# FTDI_Photosensor.net
KiCad netlist of a schematic drawn in Altium Designer
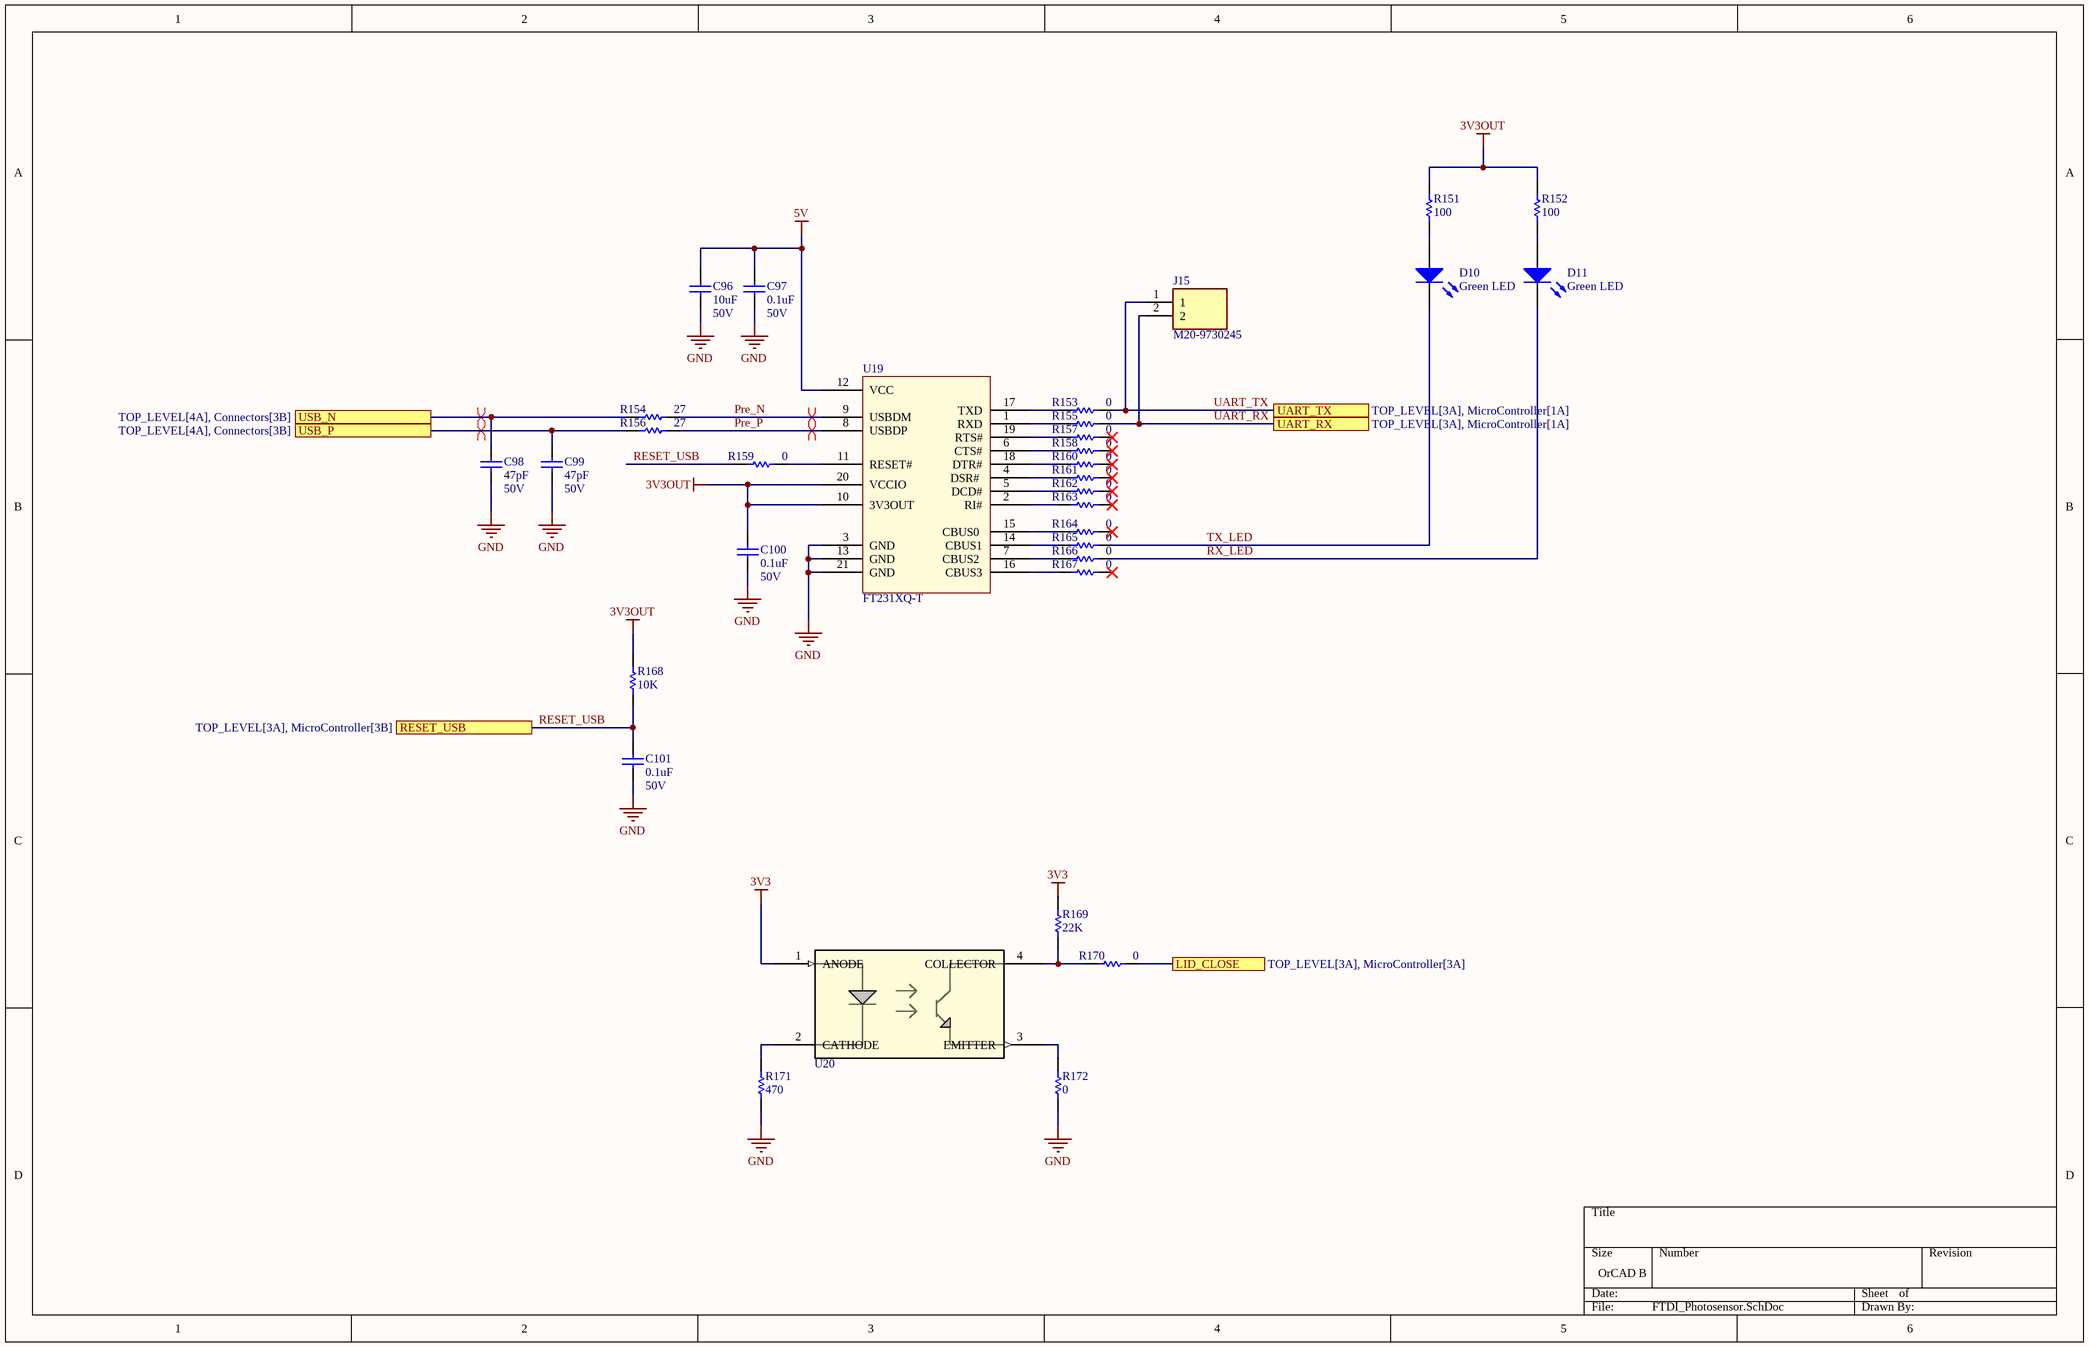
[diagram p0: FTDI_Photosensor.SchDoc]

(export (version "E")
  (design (tool "Eeschema 10.0.6"))
  (components
    (comp (ref "C96")
      (value "10uF")
      (footprint "DEFAULT_CAPACITOR_0805")
      (description "CAP CER 10UF 50V X5R 0805")
      (fields (field (name "RATING") "50V") (field (name "Comment") "GRM21BR61H106KE43L"))
      (libsource (lib "Avery Altium Llibrary") (part "GRM21BR61H106KE43L"))
    )
    (comp (ref "C97")
      (value "0.1uF")
      (footprint "DEFAULT_CAPACITOR_0805")
      (description "CAP CER 0.1UF 50V X7R 0805")
      (fields
        (field (name "MANUFACTURER") "Cal-Chip Electronics, Inc.")
        (field (name "RATING") "50V")
        (field (name "Comment") "KGM21NR71H104KT")
      )
      (libsource (lib "Avery Altium Llibrary") (part "KGM21NR71H104KT"))
    )
    (comp (ref "C98")
      (value "47pF")
      (footprint "DEFAULT_CAPACITOR_0805")
      (description "CAP CER 47PF 50V C0G/NP0 0805")
      (fields (field (name "RATING") "50V") (field (name "Comment") "C0805X470J5GACTU"))
      (libsource (lib "Avery Altium Llibrary") (part "C0805X470J5GACTU"))
    )
    (comp (ref "C99")
      (value "47pF")
      (footprint "DEFAULT_CAPACITOR_0805")
      (description "CAP CER 47PF 50V C0G/NP0 0805")
      (fields (field (name "RATING") "50V") (field (name "Comment") "C0805X470J5GACTU"))
      (libsource (lib "Avery Altium Llibrary") (part "C0805X470J5GACTU"))
    )
    (comp (ref "C100")
      (value "0.1uF")
      (footprint "DEFAULT_CAPACITOR_0805")
      (description "CAP CER 0.1UF 50V X7R 0805")
      (fields
        (field (name "MANUFACTURER") "Cal-Chip Electronics, Inc.")
        (field (name "RATING") "50V")
        (field (name "Comment") "KGM21NR71H104KT")
      )
      (libsource (lib "Avery Altium Llibrary") (part "KGM21NR71H104KT"))
    )
    (comp (ref "C101")
      (value "0.1uF")
      (footprint "DEFAULT_CAPACITOR_0805")
      (description "CAP CER 0.1UF 50V X7R 0805")
      (fields
        (field (name "MANUFACTURER") "Cal-Chip Electronics, Inc.")
        (field (name "RATING") "50V")
        (field (name "Comment") "KGM21NR71H104KT")
      )
      (libsource (lib "Avery Altium Llibrary") (part "KGM21NR71H104KT"))
    )
    (comp (ref "D10")
      (value "Green LED")
      (footprint "DEFAULT_RESISTOR_0805")
      (description "LED GREEN")
      (fields (field (name "MP") "Blue LED 0805") (field (name "Comment") "LSM0805452V"))
      (libsource (lib "Avery Schem Library") (part "LSM0805452V"))
    )
    (comp (ref "D11")
      (value "Green LED")
      (footprint "DEFAULT_RESISTOR_0805")
      (description "LED GREEN")
      (fields (field (name "MP") "Blue LED 0805") (field (name "Comment") "LSM0805452V"))
      (libsource (lib "Avery Schem Library") (part "LSM0805452V"))
    )
    (comp (ref "J15")
      (value "M20-9730245")
      (footprint "M209730245")
      (description "M20: 2 Pos Plug SIL Straight 3mm THT Connector 7mm pin Gold")
      (fields (field (name "MOUSER PART NUMBER") "855-M20-9730245"))
      (libsource (lib "Avery Altium Llibrary") (part "M20-9730245"))
    )
    (comp (ref "R151")
      (value "100")
      (footprint "DEFAULT_RESISTOR_0805")
      (description "RES SMD 100 OHM 1% 1/4W 0805")
      (fields (field (name "POWER") "1/4W") (field (name "TOLERANCE") "1%"))
      (libsource (lib "Avery Altium Llibrary") (part "CRCW0805100RFKEA"))
    )
    (comp (ref "R152")
      (value "100")
      (footprint "DEFAULT_RESISTOR_0805")
      (description "RES SMD 100 OHM 1% 1/4W 0805")
      (fields (field (name "POWER") "1/4W") (field (name "TOLERANCE") "1%"))
      (libsource (lib "Avery Altium Llibrary") (part "CRCW0805100RFKEA"))
    )
    (comp (ref "R153")
      (value "0")
      (footprint "DEFAULT_RESISTOR_0805")
      (description "RES 0 OHM JUMPER 1/8W 0805")
      (fields (field (name "POWER") "1/8W") (field (name "Comment") "RC0805JR-070RL"))
      (libsource (lib "Avery Altium Llibrary") (part "RC0805JR-070RL"))
    )
    (comp (ref "R154")
      (value "27")
      (footprint "DEFAULT_RESISTOR_0805")
      (description "RES 27 OHM 1% 1/8W 0805")
      (fields (field (name "POWER") "1/8W") (field (name "TOLERANCE") "1%"))
      (libsource (lib "Avery Altium Llibrary") (part "RMCF0805FT27R0"))
    )
    (comp (ref "R155")
      (value "0")
      (footprint "DEFAULT_RESISTOR_0805")
      (description "RES 0 OHM JUMPER 1/8W 0805")
      (fields (field (name "POWER") "1/8W") (field (name "Comment") "RC0805JR-070RL"))
      (libsource (lib "Avery Altium Llibrary") (part "RC0805JR-070RL"))
    )
    (comp (ref "R156")
      (value "27")
      (footprint "DEFAULT_RESISTOR_0805")
      (description "RES 27 OHM 1% 1/8W 0805")
      (fields (field (name "POWER") "1/8W") (field (name "TOLERANCE") "1%"))
      (libsource (lib "Avery Altium Llibrary") (part "RMCF0805FT27R0"))
    )
    (comp (ref "R157")
      (value "0")
      (footprint "DEFAULT_RESISTOR_0805")
      (description "RES 0 OHM JUMPER 1/8W 0805")
      (fields (field (name "POWER") "1/8W") (field (name "Comment") "RC0805JR-070RL"))
      (libsource (lib "Avery Altium Llibrary") (part "RC0805JR-070RL"))
    )
    (comp (ref "R158")
      (value "0")
      (footprint "DEFAULT_RESISTOR_0805")
      (description "RES 0 OHM JUMPER 1/8W 0805")
      (fields (field (name "POWER") "1/8W") (field (name "Comment") "RC0805JR-070RL"))
      (libsource (lib "Avery Altium Llibrary") (part "RC0805JR-070RL"))
    )
    (comp (ref "R159")
      (value "0")
      (footprint "DEFAULT_RESISTOR_0805")
      (description "RES 0 OHM JUMPER 1/8W 0805")
      (fields (field (name "POWER") "1/8W") (field (name "Comment") "RC0805JR-070RL"))
      (libsource (lib "Avery Altium Llibrary") (part "RC0805JR-070RL"))
    )
    (comp (ref "R160")
      (value "0")
      (footprint "DEFAULT_RESISTOR_0805")
      (description "RES 0 OHM JUMPER 1/8W 0805")
      (fields (field (name "POWER") "1/8W") (field (name "Comment") "RC0805JR-070RL"))
      (libsource (lib "Avery Altium Llibrary") (part "RC0805JR-070RL"))
    )
    (comp (ref "R161")
      (value "0")
      (footprint "DEFAULT_RESISTOR_0805")
      (description "RES 0 OHM JUMPER 1/8W 0805")
      (fields (field (name "POWER") "1/8W") (field (name "Comment") "RC0805JR-070RL"))
      (libsource (lib "Avery Altium Llibrary") (part "RC0805JR-070RL"))
    )
    (comp (ref "R162")
      (value "0")
      (footprint "DEFAULT_RESISTOR_0805")
      (description "RES 0 OHM JUMPER 1/8W 0805")
      (fields (field (name "POWER") "1/8W") (field (name "Comment") "RC0805JR-070RL"))
      (libsource (lib "Avery Altium Llibrary") (part "RC0805JR-070RL"))
    )
    (comp (ref "R163")
      (value "0")
      (footprint "DEFAULT_RESISTOR_0805")
      (description "RES 0 OHM JUMPER 1/8W 0805")
      (fields (field (name "POWER") "1/8W") (field (name "Comment") "RC0805JR-070RL"))
      (libsource (lib "Avery Altium Llibrary") (part "RC0805JR-070RL"))
    )
    (comp (ref "R164")
      (value "0")
      (footprint "DEFAULT_RESISTOR_0805")
      (description "RES 0 OHM JUMPER 1/8W 0805")
      (fields (field (name "POWER") "1/8W") (field (name "Comment") "RC0805JR-070RL"))
      (libsource (lib "Avery Altium Llibrary") (part "RC0805JR-070RL"))
    )
    (comp (ref "R165")
      (value "0")
      (footprint "DEFAULT_RESISTOR_0805")
      (description "RES 0 OHM JUMPER 1/8W 0805")
      (fields (field (name "POWER") "1/8W") (field (name "Comment") "RC0805JR-070RL"))
      (libsource (lib "Avery Altium Llibrary") (part "RC0805JR-070RL"))
    )
    (comp (ref "R166")
      (value "0")
      (footprint "DEFAULT_RESISTOR_0805")
      (description "RES 0 OHM JUMPER 1/8W 0805")
      (fields (field (name "POWER") "1/8W") (field (name "Comment") "RC0805JR-070RL"))
      (libsource (lib "Avery Altium Llibrary") (part "RC0805JR-070RL"))
    )
    (comp (ref "R167")
      (value "0")
      (footprint "DEFAULT_RESISTOR_0805")
      (description "RES 0 OHM JUMPER 1/8W 0805")
      (fields (field (name "POWER") "1/8W") (field (name "Comment") "RC0805JR-070RL"))
      (libsource (lib "Avery Altium Llibrary") (part "RC0805JR-070RL"))
    )
    (comp (ref "R168")
      (value "10K")
      (footprint "DEFAULT_RESISTOR_0805")
      (description "RES SMD 10K OHM 1% 1/4W 0805")
      (fields (field (name "POWER") "1/4W") (field (name "TOLERANCE") "1%"))
      (libsource (lib "Avery Altium Llibrary") (part "CRCW080510K0FKEA"))
    )
    (comp (ref "R169")
      (value "22K")
      (footprint "DEFAULT_RESISTOR_0805")
      (description "RES 22K OHM 1% 1/8W 0805")
      (fields (field (name "POWER") "1/8W") (field (name "TOLERANCE") "1%"))
      (libsource (lib "Avery Altium Llibrary") (part "RC0805FR-1322KL"))
    )
    (comp (ref "R170")
      (value "0")
      (footprint "DEFAULT_RESISTOR_0805")
      (description "RES 0 OHM JUMPER 1/8W 0805")
      (fields (field (name "POWER") "1/8W") (field (name "Comment") "RC0805JR-070RL"))
      (libsource (lib "Avery Altium Llibrary") (part "RC0805JR-070RL"))
    )
    (comp (ref "R171")
      (value "470")
      (footprint "DEFAULT_RESISTOR_0805")
      (description "RES 470 OHM 1% 1/8W 0805")
      (fields (field (name "POWER") "1/8W") (field (name "TOLERANCE") "1%"))
      (libsource (lib "Avery Altium Llibrary") (part "RC0805FR-07470RL"))
    )
    (comp (ref "R172")
      (value "0")
      (footprint "DEFAULT_RESISTOR_0805")
      (description "RES 0 OHM JUMPER 1/8W 0805")
      (fields (field (name "POWER") "1/8W") (field (name "Comment") "RC0805JR-070RL"))
      (libsource (lib "Avery Altium Llibrary") (part "RC0805JR-070RL"))
    )
    (comp (ref "U19")
      (value "FT231XQ-T")
      (footprint "FT231XQ-QFN20")
      (description "IC USB SERIAL FULL UART 20QFN")
      (fields (field (name "MANUFACTURER") "FTDI"))
      (libsource (lib "Avery Altium Llibrary") (part "FT231XQ-T"))
    )
    (comp (ref "U20")
      (value "EE-SX1320")
      (footprint "EE-SX1320_OMR")
      (description "Optical Sensor Through-Beam 0.079\" (2mm) Phototransistor Module, Connector, Slot Type")
      (fields (field (name "COPYRIGHT") "Copyright (C) 2026 Ultra Librarian. All rights reserved."))
      (libsource (lib "Avery Altium Llibrary") (part "EE-SX1320"))
    )
  )
  (nets
    (net (code "1") (name "/LID_CLOSE") (class "Default")
      (node (ref "R170") (pin "1") (pinfunction "1_1") (pintype "passive"))
    )
    (net (code "2") (name "/Pre_N") (class "Default")
      (node (ref "R154") (pin "1") (pinfunction "1_1") (pintype "passive"))
      (node (ref "U19") (pin "9") (pinfunction "USBDM_9") (pintype "passive"))
    )
    (net (code "3") (name "/Pre_P") (class "Default")
      (node (ref "R156") (pin "1") (pinfunction "1_1") (pintype "passive"))
      (node (ref "U19") (pin "8") (pinfunction "USBDP_8") (pintype "passive"))
    )
    (net (code "4") (name "/RESET_USB") (class "Default")
      (node (ref "C101") (pin "2") (pinfunction "2_2") (pintype "passive"))
      (node (ref "R159") (pin "2") (pinfunction "2_2") (pintype "passive"))
      (node (ref "R168") (pin "2") (pinfunction "2_2") (pintype "passive"))
    )
    (net (code "5") (name "/RX_LED") (class "Default")
      (node (ref "D11") (pin "2") (pinfunction "K_2") (pintype "passive"))
      (node (ref "R166") (pin "1") (pinfunction "1_1") (pintype "passive"))
    )
    (net (code "6") (name "/TX_LED") (class "Default")
      (node (ref "D10") (pin "2") (pinfunction "K_2") (pintype "passive"))
      (node (ref "R165") (pin "1") (pinfunction "1_1") (pintype "passive"))
    )
    (net (code "7") (name "/UART_RX") (class "Default")
      (node (ref "J15") (pin "2") (pinfunction "2_2") (pintype "passive"))
      (node (ref "R155") (pin "1") (pinfunction "1_1") (pintype "passive"))
    )
    (net (code "8") (name "/UART_TX") (class "Default")
      (node (ref "J15") (pin "1") (pinfunction "1_1") (pintype "passive"))
      (node (ref "R153") (pin "1") (pinfunction "1_1") (pintype "passive"))
    )
    (net (code "9") (name "/USB_N") (class "Default")
      (node (ref "C98") (pin "2") (pinfunction "2_2") (pintype "passive"))
      (node (ref "R154") (pin "2") (pinfunction "2_2") (pintype "passive"))
    )
    (net (code "10") (name "/USB_P") (class "Default")
      (node (ref "C99") (pin "2") (pinfunction "2_2") (pintype "passive"))
      (node (ref "R156") (pin "2") (pinfunction "2_2") (pintype "passive"))
    )
    (net (code "11") (name "3V3") (class "Default")
      (node (ref "R169") (pin "1") (pinfunction "1_1") (pintype "passive"))
      (node (ref "U20") (pin "1") (pinfunction "ANODE_1") (pintype "input"))
    )
    (net (code "12") (name "3V3OUT") (class "Default")
      (node (ref "C100") (pin "2") (pinfunction "2_2") (pintype "passive"))
      (node (ref "R151") (pin "1") (pinfunction "1_1") (pintype "passive"))
      (node (ref "R152") (pin "1") (pinfunction "1_1") (pintype "passive"))
      (node (ref "R168") (pin "1") (pinfunction "1_1") (pintype "passive"))
      (node (ref "U19") (pin "10") (pinfunction "3V3OUT_10") (pintype "passive"))
      (node (ref "U19") (pin "20") (pinfunction "VCCIO_20") (pintype "passive"))
    )
    (net (code "13") (name "5V") (class "Default")
      (node (ref "C96") (pin "2") (pinfunction "2_2") (pintype "passive"))
      (node (ref "C97") (pin "2") (pinfunction "2_2") (pintype "passive"))
      (node (ref "U19") (pin "12") (pinfunction "VCC_12") (pintype "passive"))
    )
    (net (code "14") (name "GND") (class "Default")
      (node (ref "C100") (pin "1") (pinfunction "1_1") (pintype "passive"))
      (node (ref "C101") (pin "1") (pinfunction "1_1") (pintype "passive"))
      (node (ref "C96") (pin "1") (pinfunction "1_1") (pintype "passive"))
      (node (ref "C97") (pin "1") (pinfunction "1_1") (pintype "passive"))
      (node (ref "C98") (pin "1") (pinfunction "1_1") (pintype "passive"))
      (node (ref "C99") (pin "1") (pinfunction "1_1") (pintype "passive"))
      (node (ref "R171") (pin "2") (pinfunction "2_2") (pintype "passive"))
      (node (ref "R172") (pin "2") (pinfunction "2_2") (pintype "passive"))
      (node (ref "U19") (pin "13") (pinfunction "GND_13") (pintype "passive"))
      (node (ref "U19") (pin "21") (pinfunction "GND_21") (pintype "passive"))
      (node (ref "U19") (pin "3") (pinfunction "GND_3") (pintype "passive"))
    )
    (net (code "15") (name "Net-(D10-A)") (class "Default")
      (node (ref "D10") (pin "1") (pinfunction "A_1") (pintype "passive"))
      (node (ref "R151") (pin "2") (pinfunction "2_2") (pintype "passive"))
    )
    (net (code "16") (name "Net-(D11-A)") (class "Default")
      (node (ref "D11") (pin "1") (pinfunction "A_1") (pintype "passive"))
      (node (ref "R152") (pin "2") (pinfunction "2_2") (pintype "passive"))
    )
    (net (code "17") (name "Net-(U19-CBUS0)") (class "Default")
      (node (ref "R164") (pin "2") (pinfunction "2_2") (pintype "passive"))
      (node (ref "U19") (pin "15") (pinfunction "CBUS0_15") (pintype "passive"))
    )
    (net (code "18") (name "Net-(U19-CBUS1)") (class "Default")
      (node (ref "R165") (pin "2") (pinfunction "2_2") (pintype "passive"))
      (node (ref "U19") (pin "14") (pinfunction "CBUS1_14") (pintype "passive"))
    )
    (net (code "19") (name "Net-(U19-CBUS2)") (class "Default")
      (node (ref "R166") (pin "2") (pinfunction "2_2") (pintype "passive"))
      (node (ref "U19") (pin "7") (pinfunction "CBUS2_7") (pintype "passive"))
    )
    (net (code "20") (name "Net-(U19-CBUS3)") (class "Default")
      (node (ref "R167") (pin "2") (pinfunction "2_2") (pintype "passive"))
      (node (ref "U19") (pin "16") (pinfunction "CBUS3_16") (pintype "passive"))
    )
    (net (code "21") (name "Net-(U19-CTS#)") (class "Default")
      (node (ref "R158") (pin "2") (pinfunction "2_2") (pintype "passive"))
      (node (ref "U19") (pin "6") (pinfunction "CTS#_6") (pintype "passive"))
    )
    (net (code "22") (name "Net-(U19-DCD#)") (class "Default")
      (node (ref "R162") (pin "2") (pinfunction "2_2") (pintype "passive"))
      (node (ref "U19") (pin "5") (pinfunction "DCD#_5") (pintype "passive"))
    )
    (net (code "23") (name "Net-(U19-DSR#)") (class "Default")
      (node (ref "R161") (pin "2") (pinfunction "2_2") (pintype "passive"))
      (node (ref "U19") (pin "4") (pinfunction "DSR#_4") (pintype "passive"))
    )
    (net (code "24") (name "Net-(U19-DTR#)") (class "Default")
      (node (ref "R160") (pin "2") (pinfunction "2_2") (pintype "passive"))
      (node (ref "U19") (pin "18") (pinfunction "DTR#_18") (pintype "passive"))
    )
    (net (code "25") (name "Net-(U19-RESET#)") (class "Default")
      (node (ref "R159") (pin "1") (pinfunction "1_1") (pintype "passive"))
      (node (ref "U19") (pin "11") (pinfunction "RESET#_11") (pintype "passive"))
    )
    (net (code "26") (name "Net-(U19-RI#)") (class "Default")
      (node (ref "R163") (pin "2") (pinfunction "2_2") (pintype "passive"))
      (node (ref "U19") (pin "2") (pinfunction "RI#_2") (pintype "passive"))
    )
    (net (code "27") (name "Net-(U19-RTS#)") (class "Default")
      (node (ref "R157") (pin "2") (pinfunction "2_2") (pintype "passive"))
      (node (ref "U19") (pin "19") (pinfunction "RTS#_19") (pintype "passive"))
    )
    (net (code "28") (name "Net-(U19-RXD)") (class "Default")
      (node (ref "R155") (pin "2") (pinfunction "2_2") (pintype "passive"))
      (node (ref "U19") (pin "1") (pinfunction "RXD_1") (pintype "passive"))
    )
    (net (code "29") (name "Net-(U19-TXD)") (class "Default")
      (node (ref "R153") (pin "2") (pinfunction "2_2") (pintype "passive"))
      (node (ref "U19") (pin "17") (pinfunction "TXD_17") (pintype "passive"))
    )
    (net (code "30") (name "Net-(U20-CATHODE)") (class "Default")
      (node (ref "R171") (pin "1") (pinfunction "1_1") (pintype "passive"))
      (node (ref "U20") (pin "2") (pinfunction "CATHODE_2") (pintype "passive"))
    )
    (net (code "31") (name "Net-(U20-COLLECTOR)") (class "Default")
      (node (ref "R169") (pin "2") (pinfunction "2_2") (pintype "passive"))
      (node (ref "R170") (pin "2") (pinfunction "2_2") (pintype "passive"))
      (node (ref "U20") (pin "4") (pinfunction "COLLECTOR_4") (pintype "passive"))
    )
    (net (code "32") (name "Net-(U20-EMITTER)") (class "Default")
      (node (ref "R172") (pin "1") (pinfunction "1_1") (pintype "passive"))
      (node (ref "U20") (pin "3") (pinfunction "EMITTER_3") (pintype "output"))
    )
    (net (code "33") (name "unconnected-(R157-Pad1)") (class "Default")
      (node (ref "R157") (pin "1") (pinfunction "1_1") (pintype "passive+no_connect"))
    )
    (net (code "34") (name "unconnected-(R158-Pad1)") (class "Default")
      (node (ref "R158") (pin "1") (pinfunction "1_1") (pintype "passive+no_connect"))
    )
    (net (code "35") (name "unconnected-(R160-Pad1)") (class "Default")
      (node (ref "R160") (pin "1") (pinfunction "1_1") (pintype "passive+no_connect"))
    )
    (net (code "36") (name "unconnected-(R161-Pad1)") (class "Default")
      (node (ref "R161") (pin "1") (pinfunction "1_1") (pintype "passive+no_connect"))
    )
    (net (code "37") (name "unconnected-(R162-Pad1)") (class "Default")
      (node (ref "R162") (pin "1") (pinfunction "1_1") (pintype "passive+no_connect"))
    )
    (net (code "38") (name "unconnected-(R163-Pad1)") (class "Default")
      (node (ref "R163") (pin "1") (pinfunction "1_1") (pintype "passive+no_connect"))
    )
    (net (code "39") (name "unconnected-(R164-Pad1)") (class "Default")
      (node (ref "R164") (pin "1") (pinfunction "1_1") (pintype "passive+no_connect"))
    )
    (net (code "40") (name "unconnected-(R167-Pad1)") (class "Default")
      (node (ref "R167") (pin "1") (pinfunction "1_1") (pintype "passive+no_connect"))
    )
  )
)
